# AD8065_circuit.net
KiCad netlist of a schematic drawn in Altium Designer
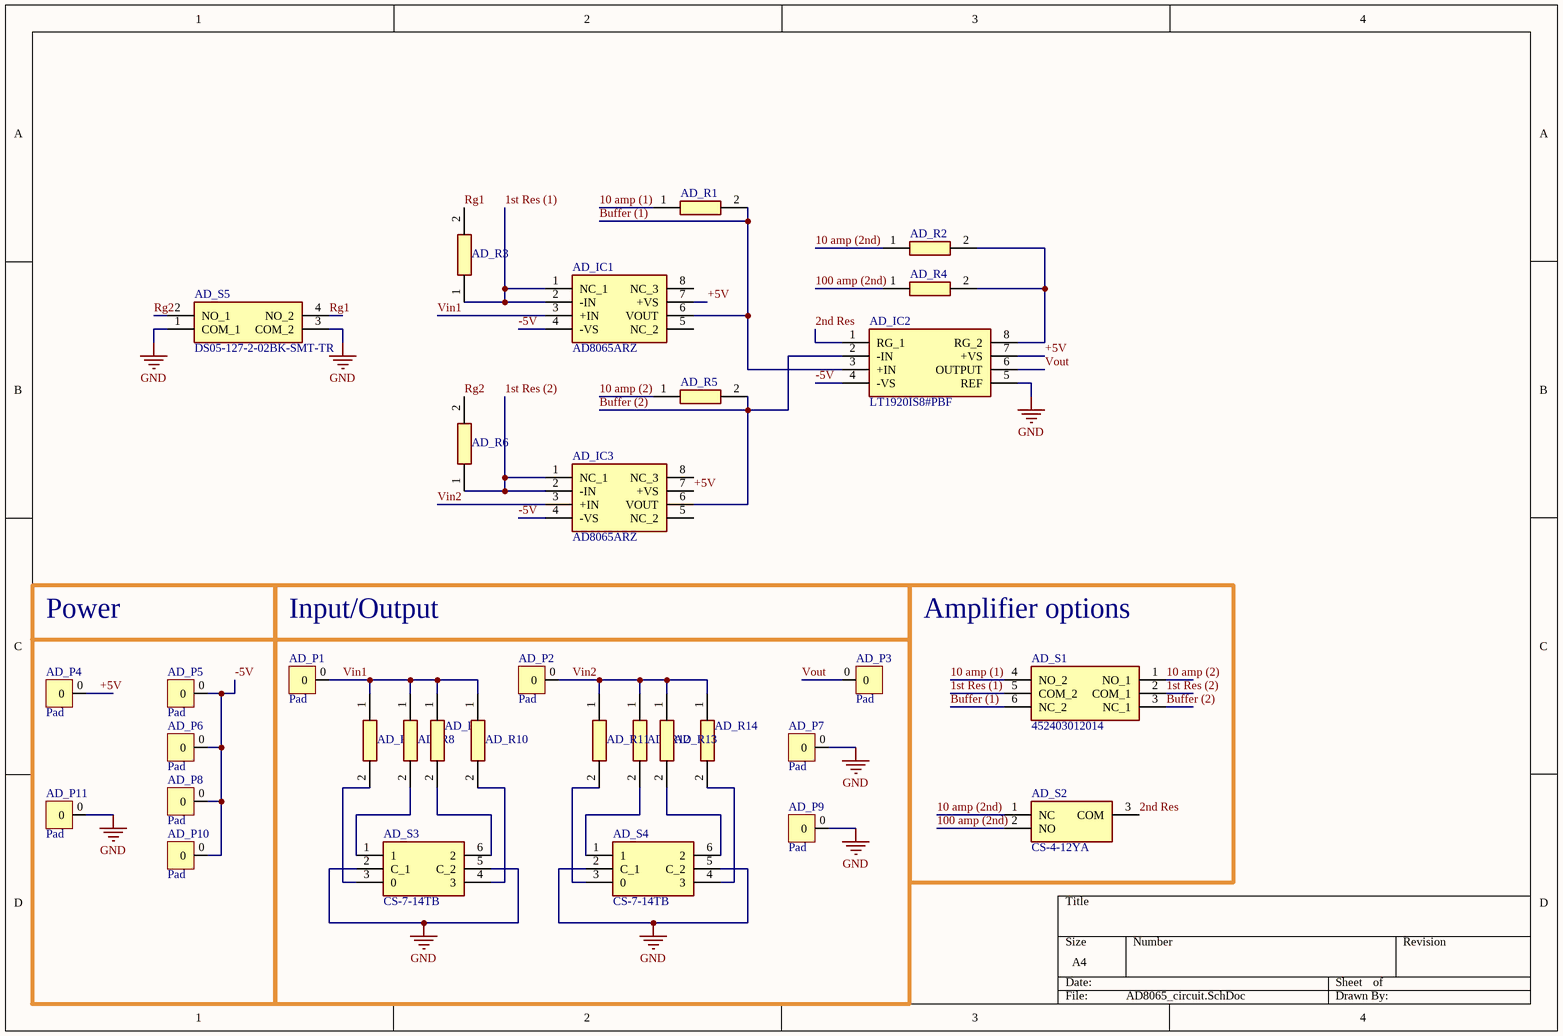
[diagram p0: AD8065_circuit.SchDoc]

(export (version "E")
  (design (tool "Eeschema 10.0.6"))
  (components
    (comp (ref "AD_IC1")
      (value "AD8065ARZ")
      (footprint "SamacSys:SOIC127P600X175-8N")
      (description "Integrated Circuit")
      (fields (field (name "MOUSER PART NUMBER") "584-AD8065ARZ"))
      (libsource (lib "SamacSys") (part "AD8065ARZ"))
    )
    (comp (ref "AD_IC2")
      (value "LT1920IS8#PBF")
      (footprint "SamacSys:SOIC127P599X175-8N")
      (description "Integrated Circuit")
      (fields (field (name "MOUSER PART NUMBER") "584-LT1920IS8#PBF"))
      (libsource (lib "SamacSys") (part "LT1920IS8#PBF"))
    )
    (comp (ref "AD_IC3")
      (value "AD8065ARZ")
      (footprint "SamacSys:SOIC127P600X175-8N")
      (description "Integrated Circuit")
      (fields (field (name "MOUSER PART NUMBER") "584-AD8065ARZ"))
      (libsource (lib "SamacSys") (part "AD8065ARZ"))
    )
    (comp (ref "AD_P1") (value "Pad") (footprint "Pad") (libsource (lib "SamacSys") (part "Pad")))
    (comp (ref "AD_P2") (value "Pad") (footprint "Pad") (libsource (lib "SamacSys") (part "Pad")))
    (comp (ref "AD_P3") (value "Pad") (footprint "Pad") (libsource (lib "") (part "Pad_1")))
    (comp (ref "AD_P4") (value "Pad") (footprint "Pad") (libsource (lib "SamacSys") (part "Pad")))
    (comp (ref "AD_P5") (value "Pad") (footprint "Pad") (libsource (lib "SamacSys") (part "Pad")))
    (comp (ref "AD_P6") (value "Pad") (footprint "Pad") (libsource (lib "SamacSys") (part "Pad")))
    (comp (ref "AD_P7") (value "Pad") (footprint "Pad") (libsource (lib "SamacSys") (part "Pad")))
    (comp (ref "AD_P8") (value "Pad") (footprint "Pad") (libsource (lib "SamacSys") (part "Pad")))
    (comp (ref "AD_P9") (value "Pad") (footprint "Pad") (libsource (lib "SamacSys") (part "Pad")))
    (comp (ref "AD_P10") (value "Pad") (footprint "Pad") (libsource (lib "SamacSys") (part "Pad")))
    (comp (ref "AD_P11") (value "Pad") (footprint "Pad") (libsource (lib "SamacSys") (part "Pad")))
    (comp (ref "AD_R1")
      (value "CRG0805F270R")
      (footprint "SamacSys:RESC2012X65N")
      (description "Resistor 270")
      (fields (field (name "MOUSER PART NUMBER") "279-CRG0805F270R"))
      (libsource (lib "SamacSys") (part "CRG0805F270R"))
    )
    (comp (ref "AD_R2")
      (value "CRG0805F4K7")
      (footprint "SamacSys:RESC2012X65N")
      (description "Resistor 4.7k")
      (fields (field (name "MOUSER PART NUMBER") "279-CRG0805F4K7"))
      (libsource (lib "SamacSys") (part "CRG0805F4K7"))
    )
    (comp (ref "AD_R3")
      (value "ERJ-HP6F20R0V")
      (footprint "SamacSys:ERJHP6D1000V")
      (description "Resistor 20")
      (libsource (lib "SamacSys") (part "ERJ-HP6F20R0V"))
    )
    (comp (ref "AD_R4")
      (value "CRG0805F330R")
      (footprint "SamacSys:RESC2012X65N")
      (description "Resistor 330")
      (fields (field (name "MOUSER PART NUMBER") "279-CRG0805F330R"))
      (libsource (lib "SamacSys") (part "CRG0805F330R"))
    )
    (comp (ref "AD_R5")
      (value "CRG0805F270R")
      (footprint "SamacSys:RESC2012X65N")
      (description "Resistor 270")
      (fields (field (name "MOUSER PART NUMBER") "279-CRG0805F270R"))
      (libsource (lib "SamacSys") (part "CRG0805F270R"))
    )
    (comp (ref "AD_R6")
      (value "ERJ-HP6F20R0V")
      (footprint "SamacSys:ERJHP6D1000V")
      (description "Resistor 20")
      (libsource (lib "SamacSys") (part "ERJ-HP6F20R0V"))
    )
    (comp (ref "AD_R7")
      (value "RH73X2A10GNTN")
      (footprint "SamacSys:RESC2013X50N")
      (description "Resistor 10G")
      (fields (field (name "MOUSER PART NUMBER") "279-RH73X2A10GNTN"))
      (libsource (lib "SamacSys") (part "RH73X2A10GNTN"))
    )
    (comp (ref "AD_R8")
      (value "RH73X2A50GNTN")
      (footprint "SamacSys:RESC2013X50N")
      (description "Resistor 50G")
      (fields (field (name "MOUSER PART NUMBER") "279-RH73X2A50GNTN"))
      (libsource (lib "SamacSys") (part "RH73X2A50GNTN"))
    )
    (comp (ref "AD_R9")
      (value "RH73H2A100MKTN")
      (footprint "SamacSys:RESC2013X50N")
      (description "Resistor 100M")
      (fields (field (name "MOUSER PART NUMBER") "279-RH73H2A100MKTN"))
      (libsource (lib "SamacSys") (part "RH73H2A100MKTN"))
    )
    (comp (ref "AD_R10")
      (value "RH73W2A1GNTN")
      (footprint "SamacSys:RESC2013X50N")
      (description "Resistor 1G")
      (fields (field (name "MOUSER PART NUMBER") "279-RH73W2A1GNTN"))
      (libsource (lib "SamacSys") (part "RH73W2A1GNTN"))
    )
    (comp (ref "AD_R11")
      (value "RH73X2A50GNTN")
      (footprint "SamacSys:RESC2013X50N")
      (description "Resistor 50G")
      (fields (field (name "MOUSER PART NUMBER") "279-RH73X2A50GNTN"))
      (libsource (lib "SamacSys") (part "RH73X2A50GNTN"))
    )
    (comp (ref "AD_R12")
      (value "RH73X2A10GNTN")
      (footprint "SamacSys:RESC2013X50N")
      (description "Resistor 10G")
      (fields (field (name "MOUSER PART NUMBER") "279-RH73X2A10GNTN"))
      (libsource (lib "SamacSys") (part "RH73X2A10GNTN"))
    )
    (comp (ref "AD_R13")
      (value "RH73W2A1GNTN")
      (footprint "SamacSys:RESC2013X50N")
      (description "Resistor 1G")
      (fields (field (name "MOUSER PART NUMBER") "279-RH73W2A1GNTN"))
      (libsource (lib "SamacSys") (part "RH73W2A1GNTN"))
    )
    (comp (ref "AD_R14")
      (value "RH73H2A100MKTN")
      (footprint "SamacSys:RESC2013X50N")
      (description "Resistor 100M")
      (fields (field (name "MOUSER PART NUMBER") "279-RH73H2A100MKTN"))
      (libsource (lib "SamacSys") (part "RH73H2A100MKTN"))
    )
    (comp (ref "AD_S1")
      (value "452403012014")
      (footprint "SamacSys:452403012014")
      (description "Switch")
      (fields (field (name "MOUSER PART NUMBER") "710-452403012014"))
      (libsource (lib "SamacSys") (part "452403012014"))
    )
    (comp (ref "AD_S2")
      (value "CS-4-12YA")
      (footprint "SamacSys:CS412YA")
      (description "Switch")
      (libsource (lib "SamacSys") (part "CS-4-12YA"))
    )
    (comp (ref "AD_S3")
      (value "CS-7-14TB")
      (footprint "SamacSys:SOP254P1000X405-6N")
      (description "Switch")
      (libsource (lib "SamacSys") (part "CS-7-14TB"))
    )
    (comp (ref "AD_S4")
      (value "CS-7-14TB")
      (footprint "SamacSys:SOP254P1000X405-6N")
      (description "Switch")
      (libsource (lib "SamacSys") (part "CS-7-14TB"))
    )
    (comp (ref "AD_S5")
      (value "DS05-127-2-02BK-SMT-TR")
      (footprint "SamacSys:DS05127202BKSMTTR")
      (description "Switch")
      (fields (field (name "MOUSER PART NUMBER") "490-DS05127202BK-STR"))
      (libsource (lib "SamacSys") (part "DS05-127-2-02BK-SMT-TR"))
    )
  )
  (nets
    (net (code "1") (name "/+5V") (class "Default")
      (node (ref "AD_IC1") (pin "7") (pinfunction "+VS_7") (pintype "passive"))
      (node (ref "AD_IC2") (pin "7") (pinfunction "+VS_7") (pintype "passive"))
      (node (ref "AD_IC3") (pin "7") (pinfunction "+VS_7") (pintype "passive"))
      (node (ref "AD_P4") (pin "0") (pinfunction "0_0") (pintype "passive"))
    )
    (net (code "2") (name "/-5V") (class "Default")
      (node (ref "AD_IC1") (pin "4") (pinfunction "-VS_4") (pintype "passive"))
      (node (ref "AD_IC2") (pin "4") (pinfunction "-VS_4") (pintype "passive"))
      (node (ref "AD_IC3") (pin "4") (pinfunction "-VS_4") (pintype "passive"))
      (node (ref "AD_P10") (pin "0") (pinfunction "0_0") (pintype "passive"))
      (node (ref "AD_P5") (pin "0") (pinfunction "0_0") (pintype "passive"))
      (node (ref "AD_P6") (pin "0") (pinfunction "0_0") (pintype "passive"))
      (node (ref "AD_P8") (pin "0") (pinfunction "0_0") (pintype "passive"))
    )
    (net (code "3") (name "/1st Res (1)") (class "Default")
      (node (ref "AD_IC1") (pin "1") (pinfunction "NC_1_1") (pintype "passive"))
      (node (ref "AD_IC1") (pin "2") (pinfunction "-IN_2") (pintype "passive"))
      (node (ref "AD_R3") (pin "1") (pinfunction "1_1") (pintype "passive"))
      (node (ref "AD_S1") (pin "5") (pinfunction "COM_2_5") (pintype "passive"))
    )
    (net (code "4") (name "/1st Res (2)") (class "Default")
      (node (ref "AD_IC3") (pin "1") (pinfunction "NC_1_1") (pintype "passive"))
      (node (ref "AD_IC3") (pin "2") (pinfunction "-IN_2") (pintype "passive"))
      (node (ref "AD_R6") (pin "1") (pinfunction "1_1") (pintype "passive"))
      (node (ref "AD_S1") (pin "2") (pinfunction "COM_1_2") (pintype "passive"))
    )
    (net (code "5") (name "/2nd Res") (class "Default")
      (node (ref "AD_IC2") (pin "1") (pinfunction "RG_1_1") (pintype "passive"))
      (node (ref "AD_S2") (pin "3") (pinfunction "COM_3") (pintype "passive"))
    )
    (net (code "6") (name "/10 amp (1)") (class "Default")
      (node (ref "AD_R1") (pin "1") (pinfunction "1_1") (pintype "passive"))
      (node (ref "AD_S1") (pin "4") (pinfunction "NO_2_4") (pintype "passive"))
    )
    (net (code "7") (name "/10 amp (2)") (class "Default")
      (node (ref "AD_R5") (pin "1") (pinfunction "1_1") (pintype "passive"))
      (node (ref "AD_S1") (pin "1") (pinfunction "NO_1_1") (pintype "passive"))
    )
    (net (code "8") (name "/10 amp (2nd)") (class "Default")
      (node (ref "AD_R2") (pin "1") (pinfunction "1_1") (pintype "passive"))
      (node (ref "AD_S2") (pin "1") (pinfunction "NC_1") (pintype "passive"))
    )
    (net (code "9") (name "/100 amp (2nd)") (class "Default")
      (node (ref "AD_R4") (pin "1") (pinfunction "1_1") (pintype "passive"))
      (node (ref "AD_S2") (pin "2") (pinfunction "NO_2") (pintype "passive"))
    )
    (net (code "10") (name "/Buffer (1)") (class "Default")
      (node (ref "AD_IC1") (pin "6") (pinfunction "VOUT_6") (pintype "passive"))
      (node (ref "AD_IC2") (pin "3") (pinfunction "+IN_3") (pintype "passive"))
      (node (ref "AD_R1") (pin "2") (pinfunction "2_2") (pintype "passive"))
      (node (ref "AD_S1") (pin "6") (pinfunction "NC_2_6") (pintype "passive"))
    )
    (net (code "11") (name "/Buffer (2)") (class "Default")
      (node (ref "AD_IC2") (pin "2") (pinfunction "-IN_2") (pintype "passive"))
      (node (ref "AD_IC3") (pin "6") (pinfunction "VOUT_6") (pintype "passive"))
      (node (ref "AD_R5") (pin "2") (pinfunction "2_2") (pintype "passive"))
      (node (ref "AD_S1") (pin "3") (pinfunction "NC_1_3") (pintype "passive"))
    )
    (net (code "12") (name "/Rg1") (class "Default")
      (node (ref "AD_R3") (pin "2") (pinfunction "2_2") (pintype "passive"))
      (node (ref "AD_S5") (pin "4") (pinfunction "NO_2_4") (pintype "passive"))
    )
    (net (code "13") (name "/Rg2") (class "Default")
      (node (ref "AD_R6") (pin "2") (pinfunction "2_2") (pintype "passive"))
      (node (ref "AD_S5") (pin "2") (pinfunction "NO_1_2") (pintype "passive"))
    )
    (net (code "14") (name "/Vin1") (class "Default")
      (node (ref "AD_IC1") (pin "3") (pinfunction "+IN_3") (pintype "passive"))
      (node (ref "AD_P1") (pin "0") (pinfunction "0_0") (pintype "passive"))
      (node (ref "AD_R10") (pin "1") (pinfunction "1_1") (pintype "passive"))
      (node (ref "AD_R7") (pin "1") (pinfunction "1_1") (pintype "passive"))
      (node (ref "AD_R8") (pin "1") (pinfunction "1_1") (pintype "passive"))
      (node (ref "AD_R9") (pin "1") (pinfunction "1_1") (pintype "passive"))
    )
    (net (code "15") (name "/Vin2") (class "Default")
      (node (ref "AD_IC3") (pin "3") (pinfunction "+IN_3") (pintype "passive"))
      (node (ref "AD_P2") (pin "0") (pinfunction "0_0") (pintype "passive"))
      (node (ref "AD_R11") (pin "1") (pinfunction "1_1") (pintype "passive"))
      (node (ref "AD_R12") (pin "1") (pinfunction "1_1") (pintype "passive"))
      (node (ref "AD_R13") (pin "1") (pinfunction "1_1") (pintype "passive"))
      (node (ref "AD_R14") (pin "1") (pinfunction "1_1") (pintype "passive"))
    )
    (net (code "16") (name "/Vout") (class "Default")
      (node (ref "AD_IC2") (pin "6") (pinfunction "OUTPUT_6") (pintype "passive"))
      (node (ref "AD_P3") (pin "0") (pinfunction "0_0") (pintype "passive"))
    )
    (net (code "17") (name "GND") (class "Default")
      (node (ref "AD_IC2") (pin "5") (pinfunction "REF_5") (pintype "passive"))
      (node (ref "AD_P11") (pin "0") (pinfunction "0_0") (pintype "passive"))
      (node (ref "AD_P7") (pin "0") (pinfunction "0_0") (pintype "passive"))
      (node (ref "AD_P9") (pin "0") (pinfunction "0_0") (pintype "passive"))
      (node (ref "AD_S3") (pin "2") (pinfunction "C_1_2") (pintype "passive"))
      (node (ref "AD_S3") (pin "5") (pinfunction "C_2_5") (pintype "passive"))
      (node (ref "AD_S4") (pin "2") (pinfunction "C_1_2") (pintype "passive"))
      (node (ref "AD_S4") (pin "5") (pinfunction "C_2_5") (pintype "passive"))
      (node (ref "AD_S5") (pin "1") (pinfunction "COM_1_1") (pintype "passive"))
      (node (ref "AD_S5") (pin "3") (pinfunction "COM_2_3") (pintype "passive"))
    )
    (net (code "18") (name "Net-(AD_IC2-RG_2)") (class "Default")
      (node (ref "AD_IC2") (pin "8") (pinfunction "RG_2_8") (pintype "passive"))
      (node (ref "AD_R2") (pin "2") (pinfunction "2_2") (pintype "passive"))
      (node (ref "AD_R4") (pin "2") (pinfunction "2_2") (pintype "passive"))
    )
    (net (code "19") (name "Net-(AD_R8-Pad2)") (class "Default")
      (node (ref "AD_R8") (pin "2") (pinfunction "2_2") (pintype "passive"))
      (node (ref "AD_S3") (pin "1") (pinfunction "1_1") (pintype "passive"))
    )
    (net (code "20") (name "Net-(AD_R12-Pad2)") (class "Default")
      (node (ref "AD_R12") (pin "2") (pinfunction "2_2") (pintype "passive"))
      (node (ref "AD_S4") (pin "1") (pinfunction "1_1") (pintype "passive"))
    )
    (net (code "21") (name "Net-(AD_S3-0)") (class "Default")
      (node (ref "AD_R7") (pin "2") (pinfunction "2_2") (pintype "passive"))
      (node (ref "AD_S3") (pin "3") (pinfunction "0_3") (pintype "passive"))
    )
    (net (code "22") (name "Net-(AD_S3-2)") (class "Default")
      (node (ref "AD_R9") (pin "2") (pinfunction "2_2") (pintype "passive"))
      (node (ref "AD_S3") (pin "6") (pinfunction "2_6") (pintype "passive"))
    )
    (net (code "23") (name "Net-(AD_S3-3)") (class "Default")
      (node (ref "AD_R10") (pin "2") (pinfunction "2_2") (pintype "passive"))
      (node (ref "AD_S3") (pin "4") (pinfunction "3_4") (pintype "passive"))
    )
    (net (code "24") (name "Net-(AD_S4-0)") (class "Default")
      (node (ref "AD_R11") (pin "2") (pinfunction "2_2") (pintype "passive"))
      (node (ref "AD_S4") (pin "3") (pinfunction "0_3") (pintype "passive"))
    )
    (net (code "25") (name "Net-(AD_S4-2)") (class "Default")
      (node (ref "AD_R13") (pin "2") (pinfunction "2_2") (pintype "passive"))
      (node (ref "AD_S4") (pin "6") (pinfunction "2_6") (pintype "passive"))
    )
    (net (code "26") (name "Net-(AD_S4-3)") (class "Default")
      (node (ref "AD_R14") (pin "2") (pinfunction "2_2") (pintype "passive"))
      (node (ref "AD_S4") (pin "4") (pinfunction "3_4") (pintype "passive"))
    )
    (net (code "27") (name "unconnected-(AD_IC1-NC_2-Pad5)") (class "Default")
      (node (ref "AD_IC1") (pin "5") (pinfunction "NC_2_5") (pintype "passive"))
    )
    (net (code "28") (name "unconnected-(AD_IC1-NC_3-Pad8)") (class "Default")
      (node (ref "AD_IC1") (pin "8") (pinfunction "NC_3_8") (pintype "passive"))
    )
    (net (code "29") (name "unconnected-(AD_IC3-NC_2-Pad5)") (class "Default")
      (node (ref "AD_IC3") (pin "5") (pinfunction "NC_2_5") (pintype "passive"))
    )
    (net (code "30") (name "unconnected-(AD_IC3-NC_3-Pad8)") (class "Default")
      (node (ref "AD_IC3") (pin "8") (pinfunction "NC_3_8") (pintype "passive"))
    )
  )
)
